# bluenrg.net
KiCad netlist of a schematic drawn in Altium Designer
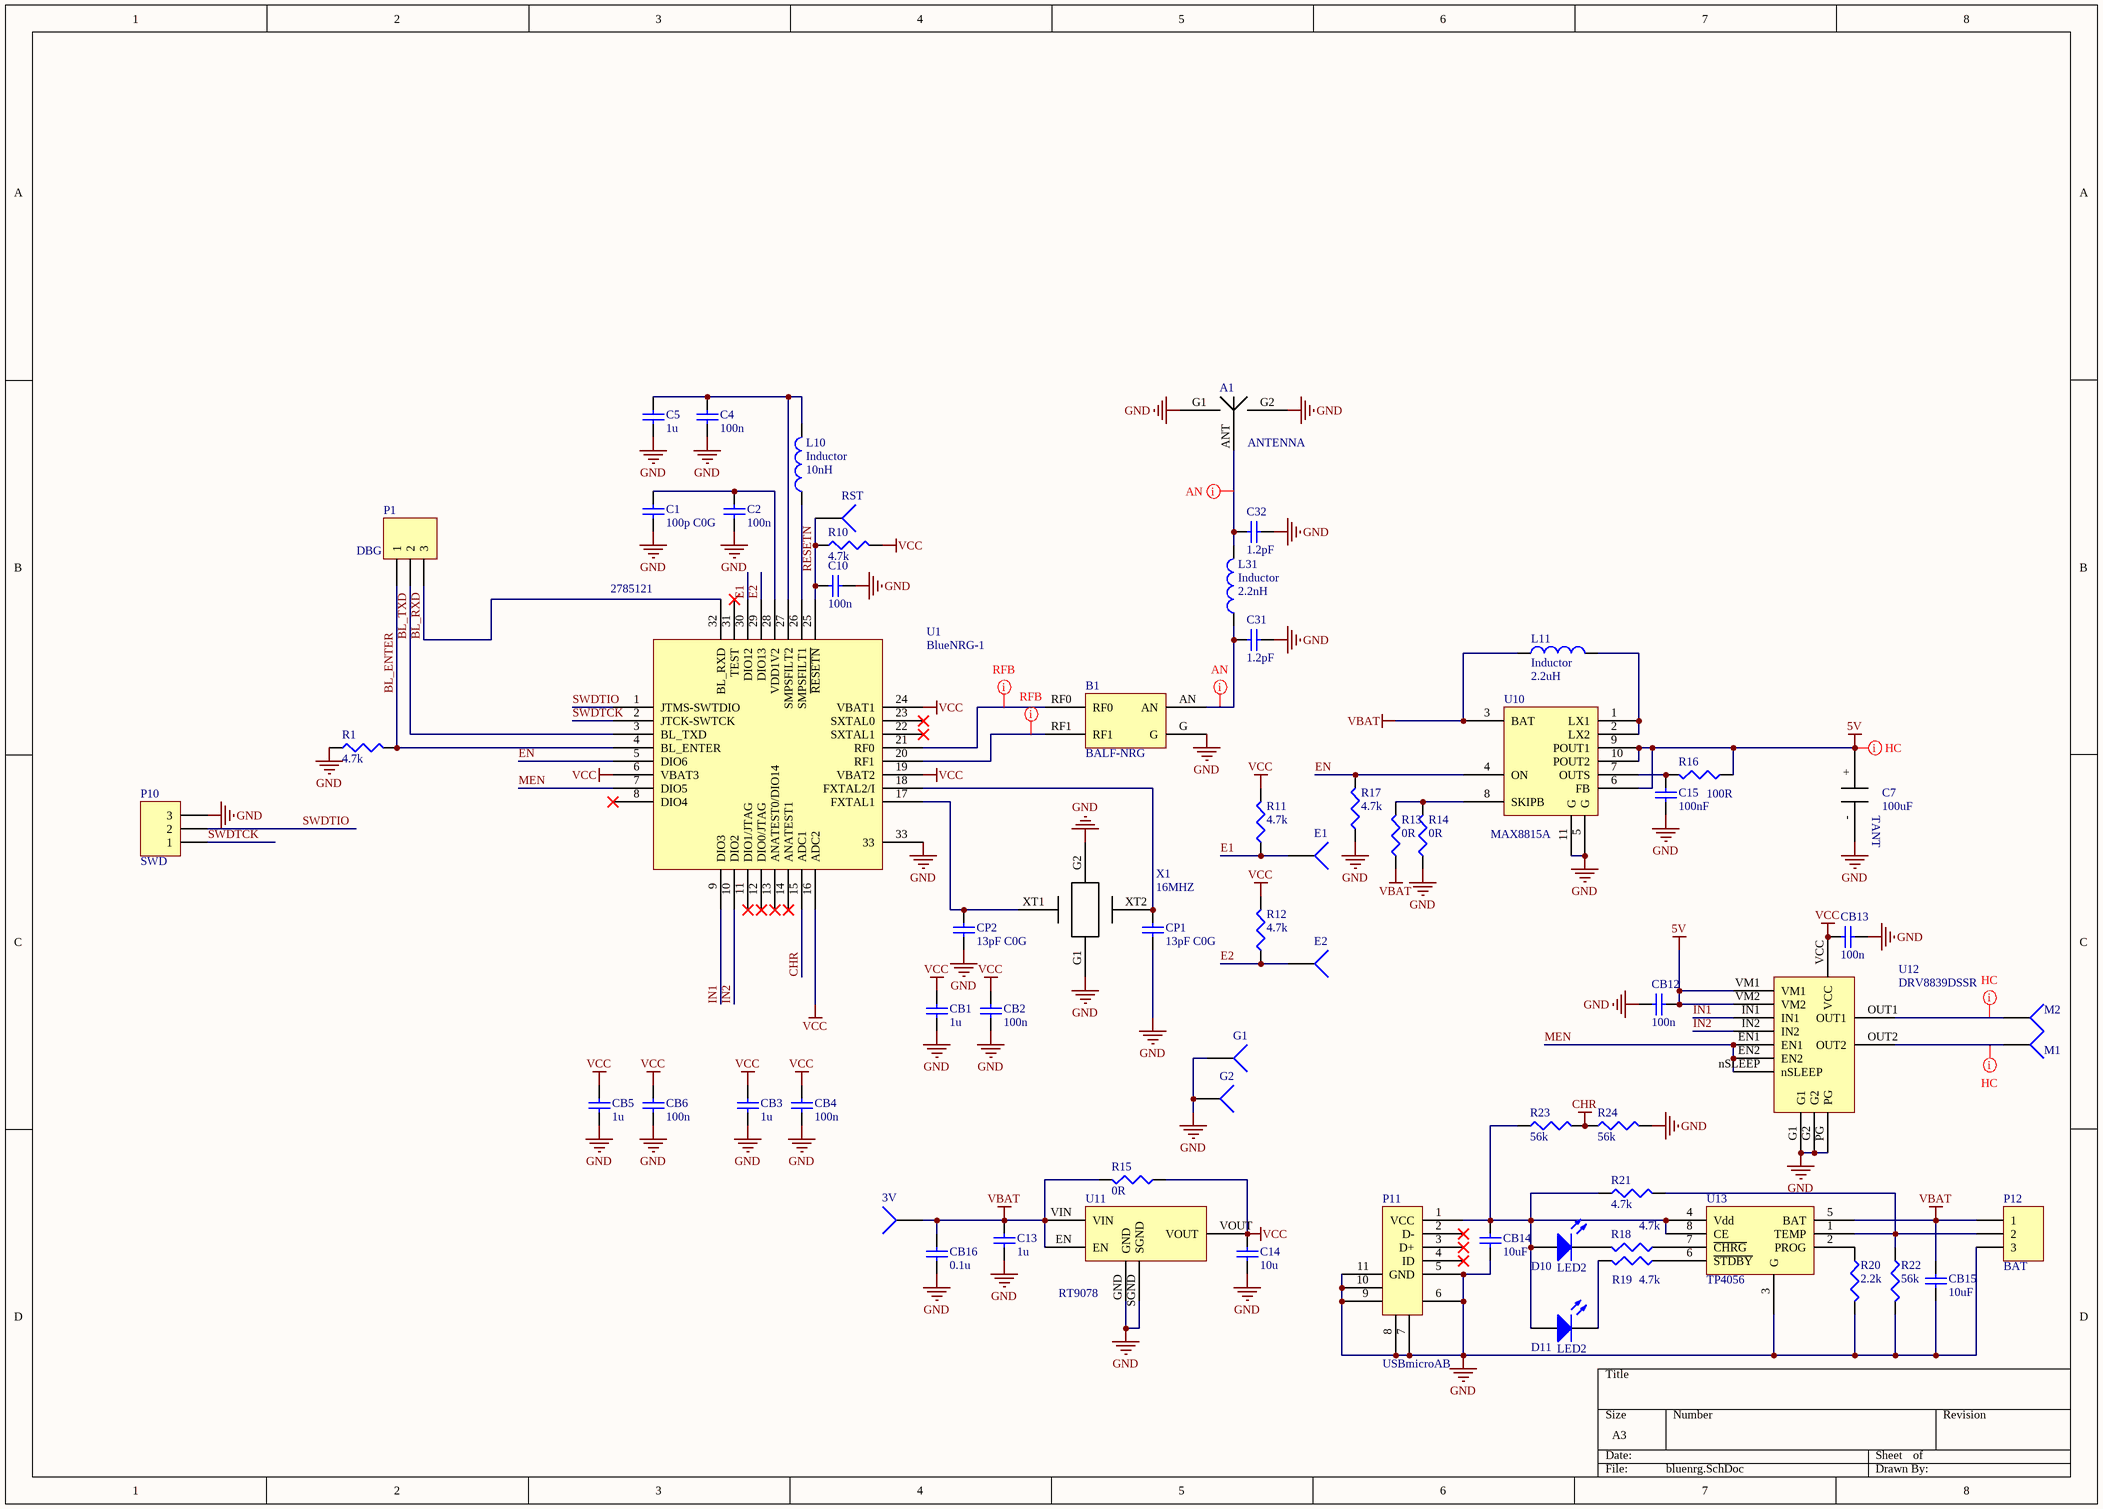
[diagram p0: bluenrg.SchDoc]

(export (version "E")
  (design (tool "Eeschema 10.0.6"))
  (components
    (comp (ref "3V")
      (value "ENC")
      (footprint "MY_PAD")
      (description "Socket")
      (fields (field (name "PUBLISHER") "Altium Limited"))
      (libsource (lib "Miscellaneous Connectors") (part "Socket"))
    )
    (comp (ref "A1") (value "ANTENNA") (footprint "sma") (libsource (lib "components") (part "ANTENNA")))
    (comp (ref "B1")
      (value "BALF-NRG")
      (footprint "BALF-NRG")
      (libsource (lib "components") (part "BALF-NRG"))
    )
    (comp (ref "C1")
      (value "100p C0G")
      (footprint "0402")
      (description "Capacitor (Semiconductor SIM Model)")
      (fields (field (name "PUBLISHER") "Altium Limited"))
      (libsource (lib "Miscellaneous Devices") (part "Cap Semi"))
    )
    (comp (ref "C2")
      (value "100n")
      (footprint "0402")
      (description "Capacitor (Semiconductor SIM Model)")
      (fields (field (name "PUBLISHER") "Altium Limited"))
      (libsource (lib "Miscellaneous Devices") (part "Cap Semi"))
    )
    (comp (ref "C4")
      (value "100n")
      (footprint "0402")
      (description "Capacitor (Semiconductor SIM Model)")
      (fields (field (name "PUBLISHER") "Altium Limited"))
      (libsource (lib "Miscellaneous Devices") (part "Cap Semi"))
    )
    (comp (ref "C5")
      (value "1u")
      (footprint "0402")
      (description "Capacitor (Semiconductor SIM Model)")
      (fields (field (name "PUBLISHER") "Altium Limited"))
      (libsource (lib "Miscellaneous Devices") (part "Cap Semi"))
    )
    (comp (ref "C7") (value "100uF") (footprint "100uf_tant") (libsource (lib "components") (part "C_TANT")))
    (comp (ref "C10")
      (value "100n")
      (footprint "0402")
      (description "Capacitor (Semiconductor SIM Model)")
      (fields (field (name "PUBLISHER") "Altium Limited"))
      (libsource (lib "Miscellaneous Devices") (part "Cap Semi"))
    )
    (comp (ref "C13")
      (value "1u")
      (footprint "MY_0603")
      (description "Capacitor (Semiconductor SIM Model)")
      (fields (field (name "PUBLISHER") "Altium Limited"))
      (libsource (lib "Miscellaneous Devices") (part "Cap Semi"))
    )
    (comp (ref "C14")
      (value "10u")
      (footprint "MY_0805")
      (description "Capacitor (Semiconductor SIM Model)")
      (fields (field (name "PUBLISHER") "Altium Limited"))
      (libsource (lib "Miscellaneous Devices") (part "Cap Semi"))
    )
    (comp (ref "C15")
      (value "100nF")
      (footprint "MY_0603")
      (description "Capacitor (Semiconductor SIM Model)")
      (fields (field (name "PUBLISHER") "Altium Limited"))
      (libsource (lib "Miscellaneous Devices") (part "Cap Semi"))
    )
    (comp (ref "C31")
      (value "1.2pF")
      (footprint "0402")
      (description "Capacitor (Semiconductor SIM Model)")
      (fields (field (name "PUBLISHER") "Altium Limited"))
      (libsource (lib "Miscellaneous Devices") (part "Cap Semi"))
    )
    (comp (ref "C32")
      (value "1.2pF")
      (footprint "0402")
      (description "Capacitor (Semiconductor SIM Model)")
      (fields (field (name "PUBLISHER") "Altium Limited"))
      (libsource (lib "Miscellaneous Devices") (part "Cap Semi"))
    )
    (comp (ref "CB1")
      (value "1u")
      (footprint "0402")
      (description "Capacitor (Semiconductor SIM Model)")
      (fields (field (name "PUBLISHER") "Altium Limited"))
      (libsource (lib "Miscellaneous Devices") (part "Cap Semi"))
    )
    (comp (ref "CB2")
      (value "100n")
      (footprint "0402")
      (description "Capacitor (Semiconductor SIM Model)")
      (fields (field (name "PUBLISHER") "Altium Limited"))
      (libsource (lib "Miscellaneous Devices") (part "Cap Semi"))
    )
    (comp (ref "CB3")
      (value "1u")
      (footprint "0402")
      (description "Capacitor (Semiconductor SIM Model)")
      (fields (field (name "PUBLISHER") "Altium Limited"))
      (libsource (lib "Miscellaneous Devices") (part "Cap Semi"))
    )
    (comp (ref "CB4")
      (value "100n")
      (footprint "0402")
      (description "Capacitor (Semiconductor SIM Model)")
      (fields (field (name "PUBLISHER") "Altium Limited"))
      (libsource (lib "Miscellaneous Devices") (part "Cap Semi"))
    )
    (comp (ref "CB5")
      (value "1u")
      (footprint "0402")
      (description "Capacitor (Semiconductor SIM Model)")
      (fields (field (name "PUBLISHER") "Altium Limited"))
      (libsource (lib "Miscellaneous Devices") (part "Cap Semi"))
    )
    (comp (ref "CB6")
      (value "100n")
      (footprint "0402")
      (description "Capacitor (Semiconductor SIM Model)")
      (fields (field (name "PUBLISHER") "Altium Limited"))
      (libsource (lib "Miscellaneous Devices") (part "Cap Semi"))
    )
    (comp (ref "CB12")
      (value "100n")
      (footprint "MY_0603")
      (description "Capacitor (Semiconductor SIM Model)")
      (fields (field (name "PUBLISHER") "Altium Limited"))
      (libsource (lib "Miscellaneous Devices") (part "Cap Semi"))
    )
    (comp (ref "CB13")
      (value "100n")
      (footprint "MY_0603")
      (description "Capacitor (Semiconductor SIM Model)")
      (fields (field (name "PUBLISHER") "Altium Limited"))
      (libsource (lib "Miscellaneous Devices") (part "Cap Semi"))
    )
    (comp (ref "CB14")
      (value "10uF")
      (footprint "MY_0805")
      (description "Capacitor (Semiconductor SIM Model)")
      (fields (field (name "PUBLISHER") "Altium Limited"))
      (libsource (lib "Miscellaneous Devices") (part "Cap Semi"))
    )
    (comp (ref "CB15")
      (value "10uF")
      (footprint "MY_0805")
      (description "Capacitor (Semiconductor SIM Model)")
      (fields (field (name "PUBLISHER") "Altium Limited"))
      (libsource (lib "Miscellaneous Devices") (part "Cap Semi"))
    )
    (comp (ref "CB16")
      (value "0.1u")
      (footprint "MY_0603")
      (description "Capacitor (Semiconductor SIM Model)")
      (fields (field (name "PUBLISHER") "Altium Limited"))
      (libsource (lib "Miscellaneous Devices") (part "Cap Semi"))
    )
    (comp (ref "CP1")
      (value "13pF C0G")
      (footprint "MY_0402")
      (description "Capacitor (Semiconductor SIM Model)")
      (fields (field (name "PUBLISHER") "Altium Limited"))
      (libsource (lib "Miscellaneous Devices") (part "Cap Semi"))
    )
    (comp (ref "CP2")
      (value "13pF C0G")
      (footprint "MY_0402")
      (description "Capacitor (Semiconductor SIM Model)")
      (fields (field (name "PUBLISHER") "Altium Limited"))
      (libsource (lib "Miscellaneous Devices") (part "Cap Semi"))
    )
    (comp (ref "D10")
      (value "LED2")
      (footprint "MY_0603")
      (description "Typical RED, GREEN, YELLOW, AMBER GaAs LED")
      (fields (field (name "PUBLISHER") "Altium Limited"))
      (libsource (lib "Miscellaneous Devices") (part "LED2"))
    )
    (comp (ref "D11")
      (value "LED2")
      (footprint "MY_0603")
      (description "Typical RED, GREEN, YELLOW, AMBER GaAs LED")
      (fields (field (name "PUBLISHER") "Altium Limited"))
      (libsource (lib "Miscellaneous Devices") (part "LED2"))
    )
    (comp (ref "E1")
      (value "ENC")
      (footprint "MY_PAD")
      (description "Socket")
      (fields (field (name "PUBLISHER") "Altium Limited"))
      (libsource (lib "Miscellaneous Connectors") (part "Socket"))
    )
    (comp (ref "E2")
      (value "ENC")
      (footprint "MY_PAD")
      (description "Socket")
      (fields (field (name "PUBLISHER") "Altium Limited"))
      (libsource (lib "Miscellaneous Connectors") (part "Socket"))
    )
    (comp (ref "G1")
      (value "ENC")
      (footprint "MY_PAD")
      (description "Socket")
      (fields (field (name "PUBLISHER") "Altium Limited"))
      (libsource (lib "Miscellaneous Connectors") (part "Socket"))
    )
    (comp (ref "G2")
      (value "ENC")
      (footprint "MY_PAD")
      (description "Socket")
      (fields (field (name "PUBLISHER") "Altium Limited"))
      (libsource (lib "Miscellaneous Connectors") (part "Socket"))
    )
    (comp (ref "L10")
      (value "Inductor")
      (footprint "MY_0805")
      (fields (field (name "ALTIUM_VALUE") "10nH") (field (name "PUBLISHER") "Altium Limited"))
      (libsource (lib "Miscellaneous Devices") (part "Inductor"))
    )
    (comp (ref "L11")
      (value "Inductor")
      (footprint "IND_4_4")
      (fields (field (name "ALTIUM_VALUE") "2.2uH") (field (name "PUBLISHER") "Altium Limited"))
      (libsource (lib "Miscellaneous Devices") (part "Inductor"))
    )
    (comp (ref "L31")
      (value "Inductor")
      (footprint "MY_0402")
      (fields (field (name "ALTIUM_VALUE") "2.2nH") (field (name "PUBLISHER") "Altium Limited"))
      (libsource (lib "Miscellaneous Devices") (part "Inductor"))
    )
    (comp (ref "M1")
      (value "M1")
      (footprint "MPAD")
      (description "Socket")
      (fields (field (name "PUBLISHER") "Altium Limited"))
      (libsource (lib "Miscellaneous Connectors") (part "Socket"))
    )
    (comp (ref "M2")
      (value "M2")
      (footprint "MPAD")
      (description "Socket")
      (fields (field (name "PUBLISHER") "Altium Limited"))
      (libsource (lib "Miscellaneous Connectors") (part "Socket"))
    )
    (comp (ref "P1")
      (value "DBG")
      (footprint "HDR1X3")
      (description "Header, 3-Pin")
      (fields (field (name "PUBLISHER") "Altium Limited"))
      (libsource (lib "Miscellaneous Connectors") (part "Header 3"))
    )
    (comp (ref "P10")
      (value "SWD")
      (footprint "HDR1X3")
      (description "Header, 3-Pin")
      (fields (field (name "PUBLISHER") "Altium Limited"))
      (libsource (lib "") (part "Header 3_1"))
    )
    (comp (ref "P11")
      (value "USBmicroAB")
      (footprint "1981584")
      (libsource (lib "components") (part "USBmicroAB"))
    )
    (comp (ref "P12")
      (value "BAT")
      (footprint "HDR1X3")
      (description "Header, 3-Pin")
      (fields (field (name "PUBLISHER") "Altium Limited"))
      (libsource (lib "") (part "Header 3_2"))
    )
    (comp (ref "R1")
      (value "4.7k")
      (footprint "MY_0603")
      (description "Resistor")
      (fields (field (name "PUBLISHER") "Altium Limited"))
      (libsource (lib "Miscellaneous Devices") (part "Res3"))
    )
    (comp (ref "R10")
      (value "4.7k")
      (footprint "MY_0603")
      (description "Resistor")
      (fields (field (name "PUBLISHER") "Altium Limited"))
      (libsource (lib "Miscellaneous Devices") (part "Res3"))
    )
    (comp (ref "R11")
      (value "4.7k")
      (footprint "MY_0603")
      (description "Resistor")
      (fields (field (name "PUBLISHER") "Altium Limited"))
      (libsource (lib "Miscellaneous Devices") (part "Res3"))
    )
    (comp (ref "R12")
      (value "4.7k")
      (footprint "MY_0603")
      (description "Resistor")
      (fields (field (name "PUBLISHER") "Altium Limited"))
      (libsource (lib "Miscellaneous Devices") (part "Res3"))
    )
    (comp (ref "R13")
      (value "0R")
      (footprint "MY_0603")
      (description "Resistor")
      (fields (field (name "PUBLISHER") "Altium Limited"))
      (libsource (lib "Miscellaneous Devices") (part "Res3"))
    )
    (comp (ref "R14")
      (value "0R")
      (footprint "MY_0603")
      (description "Resistor")
      (fields (field (name "PUBLISHER") "Altium Limited"))
      (libsource (lib "Miscellaneous Devices") (part "Res3"))
    )
    (comp (ref "R15")
      (value "0R")
      (footprint "MY_0603")
      (description "Resistor")
      (fields (field (name "PUBLISHER") "Altium Limited"))
      (libsource (lib "Miscellaneous Devices") (part "Res3"))
    )
    (comp (ref "R16")
      (value "100R")
      (footprint "MY_0603")
      (description "Resistor")
      (fields (field (name "PUBLISHER") "Altium Limited"))
      (libsource (lib "Miscellaneous Devices") (part "Res3"))
    )
    (comp (ref "R17")
      (value "4.7k")
      (footprint "MY_0603")
      (description "Resistor")
      (fields (field (name "PUBLISHER") "Altium Limited"))
      (libsource (lib "Miscellaneous Devices") (part "Res3"))
    )
    (comp (ref "R18")
      (value "4.7k")
      (footprint "MY_0603")
      (description "Resistor")
      (fields (field (name "PUBLISHER") "Altium Limited"))
      (libsource (lib "Miscellaneous Devices") (part "Res3"))
    )
    (comp (ref "R19")
      (value "4.7k")
      (footprint "MY_0603")
      (description "Resistor")
      (fields (field (name "PUBLISHER") "Altium Limited"))
      (libsource (lib "Miscellaneous Devices") (part "Res3"))
    )
    (comp (ref "R20")
      (value "2.2k")
      (footprint "MY_0603")
      (description "Resistor")
      (fields (field (name "PUBLISHER") "Altium Limited"))
      (libsource (lib "Miscellaneous Devices") (part "Res3"))
    )
    (comp (ref "R21")
      (value "4.7k")
      (footprint "MY_0603")
      (description "Resistor")
      (fields (field (name "PUBLISHER") "Altium Limited"))
      (libsource (lib "Miscellaneous Devices") (part "Res3"))
    )
    (comp (ref "R22")
      (value "56k")
      (footprint "MY_0603")
      (description "Resistor")
      (fields (field (name "PUBLISHER") "Altium Limited"))
      (libsource (lib "Miscellaneous Devices") (part "Res3"))
    )
    (comp (ref "R23")
      (value "56k")
      (footprint "MY_0603")
      (description "Resistor")
      (fields (field (name "PUBLISHER") "Altium Limited"))
      (libsource (lib "Miscellaneous Devices") (part "Res3"))
    )
    (comp (ref "R24")
      (value "56k")
      (footprint "MY_0603")
      (description "Resistor")
      (fields (field (name "PUBLISHER") "Altium Limited"))
      (libsource (lib "Miscellaneous Devices") (part "Res3"))
    )
    (comp (ref "RST")
      (value "M1")
      (footprint "MY_PAD")
      (description "Socket")
      (fields (field (name "PUBLISHER") "Altium Limited"))
      (libsource (lib "Miscellaneous Connectors") (part "Socket"))
    )
    (comp (ref "U1")
      (value "BlueNRG-1")
      (footprint "BlueNRG-1")
      (fields (field (name "SUPPLIER PART NUMBER 1") "2785121"))
      (libsource (lib "components") (part "BlueNRG-1"))
    )
    (comp (ref "U10")
      (value "MAX8815A")
      (footprint "PDQN10")
      (libsource (lib "components") (part "MAX8815A"))
    )
    (comp (ref "U11") (value "RT9078") (footprint "RT9078") (libsource (lib "components") (part "RT9078")))
    (comp (ref "U12")
      (value "DRV8839DSSR")
      (footprint "DRV8839")
      (libsource (lib "components") (part "DRV8839DSSR"))
    )
    (comp (ref "U13") (value "TP4056") (footprint "MY_SOIC8N") (libsource (lib "components") (part "TP4056")))
    (comp (ref "X1")
      (value "16MHZ")
      (footprint "16MHZ_25_20")
      (libsource (lib "components") (part "XTAL_4PIN"))
    )
  )
  (nets
    (net (code "1") (name "/BL_ENTER") (class "Default")
      (node (ref "P1") (pin "1") (pinfunction "1_1") (pintype "passive"))
      (node (ref "R1") (pin "2") (pinfunction "2_2") (pintype "passive"))
      (node (ref "U1") (pin "4") (pinfunction "BL_ENTER_4") (pintype "passive"))
    )
    (net (code "2") (name "/BL_RXD") (class "Default")
      (node (ref "P1") (pin "3") (pinfunction "3_3") (pintype "passive"))
      (node (ref "U1") (pin "32") (pinfunction "BL_RXD_32") (pintype "passive"))
    )
    (net (code "3") (name "/BL_TXD") (class "Default")
      (node (ref "P1") (pin "2") (pinfunction "2_2") (pintype "passive"))
      (node (ref "U1") (pin "3") (pinfunction "BL_TXD_3") (pintype "passive"))
    )
    (net (code "4") (name "/E1") (class "Default")
      (node (ref "E1") (pin "1") (pinfunction "1_1") (pintype "passive"))
      (node (ref "R11") (pin "1") (pinfunction "1_1") (pintype "passive"))
      (node (ref "U1") (pin "30") (pinfunction "DIO12_30") (pintype "passive"))
    )
    (net (code "5") (name "/E2") (class "Default")
      (node (ref "E2") (pin "1") (pinfunction "1_1") (pintype "passive"))
      (node (ref "R12") (pin "1") (pinfunction "1_1") (pintype "passive"))
      (node (ref "U1") (pin "29") (pinfunction "DIO13_29") (pintype "passive"))
    )
    (net (code "6") (name "/EN") (class "Default")
      (node (ref "R17") (pin "2") (pinfunction "2_2") (pintype "passive"))
      (node (ref "U1") (pin "5") (pinfunction "DIO6_5") (pintype "passive"))
      (node (ref "U10") (pin "4") (pinfunction "ON_4") (pintype "passive"))
    )
    (net (code "7") (name "/IN1") (class "Default")
      (node (ref "U1") (pin "9") (pinfunction "DIO3_9") (pintype "passive"))
      (node (ref "U12") (pin "IN1") (pinfunction "IN1_IN1") (pintype "passive"))
    )
    (net (code "8") (name "/IN2") (class "Default")
      (node (ref "U1") (pin "10") (pinfunction "DIO2_10") (pintype "passive"))
      (node (ref "U12") (pin "IN2") (pinfunction "IN2_IN2") (pintype "passive"))
    )
    (net (code "9") (name "/MEN") (class "Default")
      (node (ref "U1") (pin "7") (pinfunction "DIO5_7") (pintype "passive"))
      (node (ref "U12") (pin "EN1") (pinfunction "EN1_EN1") (pintype "passive"))
      (node (ref "U12") (pin "EN2") (pinfunction "EN2_EN2") (pintype "passive"))
      (node (ref "U12") (pin "nSLEEP") (pinfunction "nSLEEP_nSLEEP") (pintype "passive"))
    )
    (net (code "10") (name "/RESETN") (class "Default")
      (node (ref "C10") (pin "2") (pinfunction "2_2") (pintype "passive"))
      (node (ref "R10") (pin "1") (pinfunction "1_1") (pintype "passive"))
      (node (ref "RST") (pin "1") (pinfunction "1_1") (pintype "passive"))
      (node (ref "U1") (pin "25") (pinfunction "~{RESETN}_25") (pintype "passive"))
    )
    (net (code "11") (name "/SWDTCK") (class "Default")
      (node (ref "P10") (pin "1") (pinfunction "1_1") (pintype "passive"))
      (node (ref "U1") (pin "2") (pinfunction "JTCK-SWTCK_2") (pintype "passive"))
    )
    (net (code "12") (name "/SWDTIO") (class "Default")
      (node (ref "P10") (pin "2") (pinfunction "2_2") (pintype "passive"))
      (node (ref "U1") (pin "1") (pinfunction "JTMS-SWTDIO_1") (pintype "passive"))
    )
    (net (code "13") (name "5V") (class "Default")
      (node (ref "C7") (pin "+") (pinfunction "+_+") (pintype "passive"))
      (node (ref "CB12") (pin "2") (pinfunction "2_2") (pintype "passive"))
      (node (ref "R16") (pin "1") (pinfunction "1_1") (pintype "passive"))
      (node (ref "U10") (pin "10") (pinfunction "POUT2_10") (pintype "passive"))
      (node (ref "U10") (pin "6") (pinfunction "FB_6") (pintype "passive"))
      (node (ref "U10") (pin "9") (pinfunction "POUT1_9") (pintype "passive"))
      (node (ref "U12") (pin "VM1") (pinfunction "VM1_VM1") (pintype "passive"))
      (node (ref "U12") (pin "VM2") (pinfunction "VM2_VM2") (pintype "passive"))
    )
    (net (code "14") (name "CHR") (class "Default")
      (node (ref "R23") (pin "2") (pinfunction "2_2") (pintype "passive"))
      (node (ref "R24") (pin "1") (pinfunction "1_1") (pintype "passive"))
      (node (ref "U1") (pin "15") (pinfunction "ADC1_15") (pintype "passive"))
    )
    (net (code "15") (name "GND") (class "Default")
      (node (ref "A1") (pin "G1") (pinfunction "G1_G1") (pintype "passive"))
      (node (ref "A1") (pin "G2") (pinfunction "G2_G2") (pintype "passive"))
      (node (ref "B1") (pin "G") (pinfunction "G_G") (pintype "passive"))
      (node (ref "C1") (pin "1") (pinfunction "1_1") (pintype "passive"))
      (node (ref "C10") (pin "1") (pinfunction "1_1") (pintype "passive"))
      (node (ref "C13") (pin "1") (pinfunction "1_1") (pintype "passive"))
      (node (ref "C14") (pin "1") (pinfunction "1_1") (pintype "passive"))
      (node (ref "C15") (pin "1") (pinfunction "1_1") (pintype "passive"))
      (node (ref "C2") (pin "1") (pinfunction "1_1") (pintype "passive"))
      (node (ref "C31") (pin "2") (pinfunction "2_2") (pintype "passive"))
      (node (ref "C32") (pin "2") (pinfunction "2_2") (pintype "passive"))
      (node (ref "C4") (pin "1") (pinfunction "1_1") (pintype "passive"))
      (node (ref "C5") (pin "1") (pinfunction "1_1") (pintype "passive"))
      (node (ref "C7") (pin "-") (pinfunction "-_-") (pintype "passive"))
      (node (ref "CB1") (pin "1") (pinfunction "1_1") (pintype "passive"))
      (node (ref "CB12") (pin "1") (pinfunction "1_1") (pintype "passive"))
      (node (ref "CB13") (pin "2") (pinfunction "2_2") (pintype "passive"))
      (node (ref "CB14") (pin "1") (pinfunction "1_1") (pintype "passive"))
      (node (ref "CB15") (pin "1") (pinfunction "1_1") (pintype "passive"))
      (node (ref "CB16") (pin "1") (pinfunction "1_1") (pintype "passive"))
      (node (ref "CB2") (pin "1") (pinfunction "1_1") (pintype "passive"))
      (node (ref "CB3") (pin "1") (pinfunction "1_1") (pintype "passive"))
      (node (ref "CB4") (pin "1") (pinfunction "1_1") (pintype "passive"))
      (node (ref "CB5") (pin "1") (pinfunction "1_1") (pintype "passive"))
      (node (ref "CB6") (pin "1") (pinfunction "1_1") (pintype "passive"))
      (node (ref "CP1") (pin "1") (pinfunction "1_1") (pintype "passive"))
      (node (ref "CP2") (pin "1") (pinfunction "1_1") (pintype "passive"))
      (node (ref "G1") (pin "1") (pinfunction "1_1") (pintype "passive"))
      (node (ref "G2") (pin "1") (pinfunction "1_1") (pintype "passive"))
      (node (ref "P10") (pin "3") (pinfunction "3_3") (pintype "passive"))
      (node (ref "P11") (pin "10") (pintype "passive"))
      (node (ref "P11") (pin "11") (pintype "passive"))
      (node (ref "P11") (pin "5") (pinfunction "GND_5") (pintype "passive"))
      (node (ref "P11") (pin "6") (pintype "passive"))
      (node (ref "P11") (pin "7") (pintype "passive"))
      (node (ref "P11") (pin "8") (pintype "passive"))
      (node (ref "P11") (pin "9") (pintype "passive"))
      (node (ref "P12") (pin "3") (pinfunction "3_3") (pintype "passive"))
      (node (ref "R1") (pin "1") (pinfunction "1_1") (pintype "passive"))
      (node (ref "R14") (pin "1") (pinfunction "1_1") (pintype "passive"))
      (node (ref "R17") (pin "1") (pinfunction "1_1") (pintype "passive"))
      (node (ref "R20") (pin "2") (pinfunction "2_2") (pintype "passive"))
      (node (ref "R22") (pin "2") (pinfunction "2_2") (pintype "passive"))
      (node (ref "R24") (pin "2") (pinfunction "2_2") (pintype "passive"))
      (node (ref "U1") (pin "33") (pinfunction "33_33") (pintype "passive"))
      (node (ref "U10") (pin "11") (pinfunction "G_11") (pintype "passive"))
      (node (ref "U10") (pin "5") (pinfunction "G_5") (pintype "passive"))
      (node (ref "U11") (pin "GND") (pinfunction "GND_GND") (pintype "passive"))
      (node (ref "U11") (pin "SGND") (pinfunction "SGND_SGND") (pintype "passive"))
      (node (ref "U12") (pin "G1") (pinfunction "G1_G1") (pintype "passive"))
      (node (ref "U12") (pin "G2") (pinfunction "G2_G2") (pintype "passive"))
      (node (ref "U12") (pin "PG") (pinfunction "PG_PG") (pintype "passive"))
      (node (ref "U13") (pin "3") (pinfunction "G_3") (pintype "passive"))
      (node (ref "X1") (pin "G1") (pinfunction "G1_G1") (pintype "passive"))
      (node (ref "X1") (pin "G2") (pinfunction "G2_G2") (pintype "passive"))
    )
    (net (code "16") (name "Net-(A1-PadANT)") (class "Default")
      (node (ref "A1") (pin "ANT") (pinfunction "ANT_ANT") (pintype "passive"))
      (node (ref "C32") (pin "1") (pinfunction "1_1") (pintype "passive"))
      (node (ref "L31") (pin "2") (pinfunction "2_2") (pintype "passive"))
    )
    (net (code "17") (name "Net-(B1-PadAN)") (class "Default")
      (node (ref "B1") (pin "AN") (pinfunction "AN_AN") (pintype "passive"))
      (node (ref "C31") (pin "1") (pinfunction "1_1") (pintype "passive"))
      (node (ref "L31") (pin "1") (pinfunction "1_1") (pintype "passive"))
    )
    (net (code "18") (name "Net-(D10-A)") (class "Default")
      (node (ref "CB14") (pin "2") (pinfunction "2_2") (pintype "passive"))
      (node (ref "D10") (pin "1") (pinfunction "A_1") (pintype "passive"))
      (node (ref "D11") (pin "1") (pinfunction "A_1") (pintype "passive"))
      (node (ref "P11") (pin "1") (pinfunction "VCC_1") (pintype "passive"))
      (node (ref "R21") (pin "1") (pinfunction "1_1") (pintype "passive"))
      (node (ref "R23") (pin "1") (pinfunction "1_1") (pintype "passive"))
      (node (ref "U13") (pin "4") (pinfunction "Vdd_4") (pintype "passive"))
      (node (ref "U13") (pin "8") (pinfunction "CE_8") (pintype "passive"))
    )
    (net (code "19") (name "Net-(D10-K)") (class "Default")
      (node (ref "D10") (pin "2") (pinfunction "K_2") (pintype "passive"))
      (node (ref "R18") (pin "2") (pinfunction "2_2") (pintype "passive"))
    )
    (net (code "20") (name "Net-(D11-K)") (class "Default")
      (node (ref "D11") (pin "2") (pinfunction "K_2") (pintype "passive"))
      (node (ref "R19") (pin "2") (pinfunction "2_2") (pintype "passive"))
    )
    (net (code "21") (name "Net-(M1-Pad1)") (class "Default")
      (node (ref "M1") (pin "1") (pinfunction "1_1") (pintype "passive"))
      (node (ref "U12") (pin "OUT2") (pinfunction "OUT2_OUT2") (pintype "passive"))
    )
    (net (code "22") (name "Net-(M2-Pad1)") (class "Default")
      (node (ref "M2") (pin "1") (pinfunction "1_1") (pintype "passive"))
      (node (ref "U12") (pin "OUT1") (pinfunction "OUT1_OUT1") (pintype "passive"))
    )
    (net (code "23") (name "Net-(U1-FXTAL1)") (class "Default")
      (node (ref "CP2") (pin "2") (pinfunction "2_2") (pintype "passive"))
      (node (ref "U1") (pin "17") (pinfunction "FXTAL1_17") (pintype "passive"))
      (node (ref "X1") (pin "XT1") (pinfunction "XT1_XT1") (pintype "passive"))
    )
    (net (code "24") (name "Net-(U1-FXTAL2{slash}I)") (class "Default")
      (node (ref "CP1") (pin "2") (pinfunction "2_2") (pintype "passive"))
      (node (ref "U1") (pin "18") (pinfunction "FXTAL2/I_18") (pintype "passive"))
      (node (ref "X1") (pin "XT2") (pinfunction "XT2_XT2") (pintype "passive"))
    )
    (net (code "25") (name "Net-(U1-RF0)") (class "Default")
      (node (ref "B1") (pin "RF0") (pinfunction "RF0_RF0") (pintype "passive"))
      (node (ref "U1") (pin "21") (pinfunction "RF0_21") (pintype "passive"))
    )
    (net (code "26") (name "Net-(U1-RF1)") (class "Default")
      (node (ref "B1") (pin "RF1") (pinfunction "RF1_RF1") (pintype "passive"))
      (node (ref "U1") (pin "20") (pinfunction "RF1_20") (pintype "passive"))
    )
    (net (code "27") (name "Net-(U1-SMPSFILT1)") (class "Default")
      (node (ref "L10") (pin "1") (pinfunction "1_1") (pintype "passive"))
      (node (ref "U1") (pin "26") (pinfunction "SMPSFILT1_26") (pintype "passive"))
    )
    (net (code "28") (name "Net-(U1-SMPSFILT2)") (class "Default")
      (node (ref "C4") (pin "2") (pinfunction "2_2") (pintype "passive"))
      (node (ref "C5") (pin "2") (pinfunction "2_2") (pintype "passive"))
      (node (ref "L10") (pin "2") (pinfunction "2_2") (pintype "passive"))
      (node (ref "U1") (pin "27") (pinfunction "SMPSFILT2_27") (pintype "passive"))
    )
    (net (code "29") (name "Net-(U1-VDD1V2)") (class "Default")
      (node (ref "C1") (pin "2") (pinfunction "2_2") (pintype "passive"))
      (node (ref "C2") (pin "2") (pinfunction "2_2") (pintype "passive"))
      (node (ref "U1") (pin "28") (pinfunction "VDD1V2_28") (pintype "passive"))
    )
    (net (code "30") (name "Net-(U10-LX1)") (class "Default")
      (node (ref "L11") (pin "2") (pinfunction "2_2") (pintype "passive"))
      (node (ref "U10") (pin "1") (pinfunction "LX1_1") (pintype "passive"))
      (node (ref "U10") (pin "2") (pinfunction "LX2_2") (pintype "passive"))
    )
    (net (code "31") (name "Net-(U10-OUTS)") (class "Default")
      (node (ref "C15") (pin "2") (pinfunction "2_2") (pintype "passive"))
      (node (ref "R16") (pin "2") (pinfunction "2_2") (pintype "passive"))
      (node (ref "U10") (pin "7") (pinfunction "OUTS_7") (pintype "passive"))
    )
    (net (code "32") (name "Net-(U10-SKIPB)") (class "Default")
      (node (ref "R13") (pin "2") (pinfunction "2_2") (pintype "passive"))
      (node (ref "R14") (pin "2") (pinfunction "2_2") (pintype "passive"))
      (node (ref "U10") (pin "8") (pinfunction "SKIPB_8") (pintype "passive"))
    )
    (net (code "33") (name "Net-(U13-PROG)") (class "Default")
      (node (ref "R20") (pin "1") (pinfunction "1_1") (pintype "passive"))
      (node (ref "U13") (pin "2") (pinfunction "PROG_2") (pintype "passive"))
    )
    (net (code "34") (name "Net-(U13-TEMP)") (class "Default")
      (node (ref "P12") (pin "2") (pinfunction "2_2") (pintype "passive"))
      (node (ref "R21") (pin "2") (pinfunction "2_2") (pintype "passive"))
      (node (ref "R22") (pin "1") (pinfunction "1_1") (pintype "passive"))
      (node (ref "U13") (pin "1") (pinfunction "TEMP_1") (pintype "passive"))
    )
    (net (code "35") (name "Net-(U13-~{CHRG})") (class "Default")
      (node (ref "R18") (pin "1") (pinfunction "1_1") (pintype "passive"))
      (node (ref "U13") (pin "7") (pinfunction "~{CHRG}_7") (pintype "passive"))
    )
    (net (code "36") (name "Net-(U13-~{STDBY})") (class "Default")
      (node (ref "R19") (pin "1") (pinfunction "1_1") (pintype "passive"))
      (node (ref "U13") (pin "6") (pinfunction "~{STDBY}_6") (pintype "passive"))
    )
    (net (code "37") (name "VBAT") (class "Default")
      (node (ref "3V") (pin "1") (pinfunction "1_1") (pintype "passive"))
      (node (ref "C13") (pin "2") (pinfunction "2_2") (pintype "passive"))
      (node (ref "CB15") (pin "2") (pinfunction "2_2") (pintype "passive"))
      (node (ref "CB16") (pin "2") (pinfunction "2_2") (pintype "passive"))
      (node (ref "L11") (pin "1") (pinfunction "1_1") (pintype "passive"))
      (node (ref "P12") (pin "1") (pinfunction "1_1") (pintype "passive"))
      (node (ref "R13") (pin "1") (pinfunction "1_1") (pintype "passive"))
      (node (ref "R15") (pin "2") (pinfunction "2_2") (pintype "passive"))
      (node (ref "U10") (pin "3") (pinfunction "BAT_3") (pintype "passive"))
      (node (ref "U11") (pin "EN") (pinfunction "EN_EN") (pintype "passive"))
      (node (ref "U11") (pin "VIN") (pinfunction "VIN_VIN") (pintype "passive"))
      (node (ref "U13") (pin "5") (pinfunction "BAT_5") (pintype "passive"))
    )
    (net (code "38") (name "VCC") (class "Default")
      (node (ref "C14") (pin "2") (pinfunction "2_2") (pintype "passive"))
      (node (ref "CB1") (pin "2") (pinfunction "2_2") (pintype "passive"))
      (node (ref "CB13") (pin "1") (pinfunction "1_1") (pintype "passive"))
      (node (ref "CB2") (pin "2") (pinfunction "2_2") (pintype "passive"))
      (node (ref "CB3") (pin "2") (pinfunction "2_2") (pintype "passive"))
      (node (ref "CB4") (pin "2") (pinfunction "2_2") (pintype "passive"))
      (node (ref "CB5") (pin "2") (pinfunction "2_2") (pintype "passive"))
      (node (ref "CB6") (pin "2") (pinfunction "2_2") (pintype "passive"))
      (node (ref "R10") (pin "2") (pinfunction "2_2") (pintype "passive"))
      (node (ref "R11") (pin "2") (pinfunction "2_2") (pintype "passive"))
      (node (ref "R12") (pin "2") (pinfunction "2_2") (pintype "passive"))
      (node (ref "R15") (pin "1") (pinfunction "1_1") (pintype "passive"))
      (node (ref "U1") (pin "16") (pinfunction "ADC2_16") (pintype "passive"))
      (node (ref "U1") (pin "19") (pinfunction "VBAT2_19") (pintype "passive"))
      (node (ref "U1") (pin "24") (pinfunction "VBAT1_24") (pintype "passive"))
      (node (ref "U1") (pin "6") (pinfunction "VBAT3_6") (pintype "passive"))
      (node (ref "U11") (pin "VOUT") (pinfunction "VOUT_VOUT") (pintype "passive"))
      (node (ref "U12") (pin "VCC") (pinfunction "VCC_VCC") (pintype "passive"))
    )
    (net (code "39") (name "unconnected-(P11-D+-Pad3)") (class "Default")
      (node (ref "P11") (pin "3") (pinfunction "D+_3") (pintype "passive+no_connect"))
    )
    (net (code "40") (name "unconnected-(P11-D--Pad2)") (class "Default")
      (node (ref "P11") (pin "2") (pinfunction "D-_2") (pintype "passive+no_connect"))
    )
    (net (code "41") (name "unconnected-(P11-ID-Pad4)") (class "Default")
      (node (ref "P11") (pin "4") (pinfunction "ID_4") (pintype "passive+no_connect"))
    )
    (net (code "42") (name "unconnected-(U1-ANATEST0{slash}DIO14-Pad13)") (class "Default")
      (node (ref "U1") (pin "13") (pinfunction "ANATEST0/DIO14_13") (pintype "passive+no_connect"))
    )
    (net (code "43") (name "unconnected-(U1-ANATEST1-Pad14)") (class "Default")
      (node (ref "U1") (pin "14") (pinfunction "ANATEST1_14") (pintype "passive+no_connect"))
    )
    (net (code "44") (name "unconnected-(U1-DIO0{slash}JTAG-Pad12)") (class "Default")
      (node (ref "U1") (pin "12") (pinfunction "DIO0/JTAG_12") (pintype "passive+no_connect"))
    )
    (net (code "45") (name "unconnected-(U1-DIO1{slash}JTAG-Pad11)") (class "Default")
      (node (ref "U1") (pin "11") (pinfunction "DIO1/JTAG_11") (pintype "passive+no_connect"))
    )
    (net (code "46") (name "unconnected-(U1-DIO4-Pad8)") (class "Default")
      (node (ref "U1") (pin "8") (pinfunction "DIO4_8") (pintype "passive+no_connect"))
    )
    (net (code "47") (name "unconnected-(U1-SXTAL0-Pad23)") (class "Default")
      (node (ref "U1") (pin "23") (pinfunction "SXTAL0_23") (pintype "passive+no_connect"))
    )
    (net (code "48") (name "unconnected-(U1-SXTAL1-Pad22)") (class "Default")
      (node (ref "U1") (pin "22") (pinfunction "SXTAL1_22") (pintype "passive+no_connect"))
    )
    (net (code "49") (name "unconnected-(U1-TEST-Pad31)") (class "Default")
      (node (ref "U1") (pin "31") (pinfunction "TEST_31") (pintype "passive+no_connect"))
    )
  )
)
